# lunchbeats_-_OK.net
KiCad netlist of a schematic drawn in EAGLE
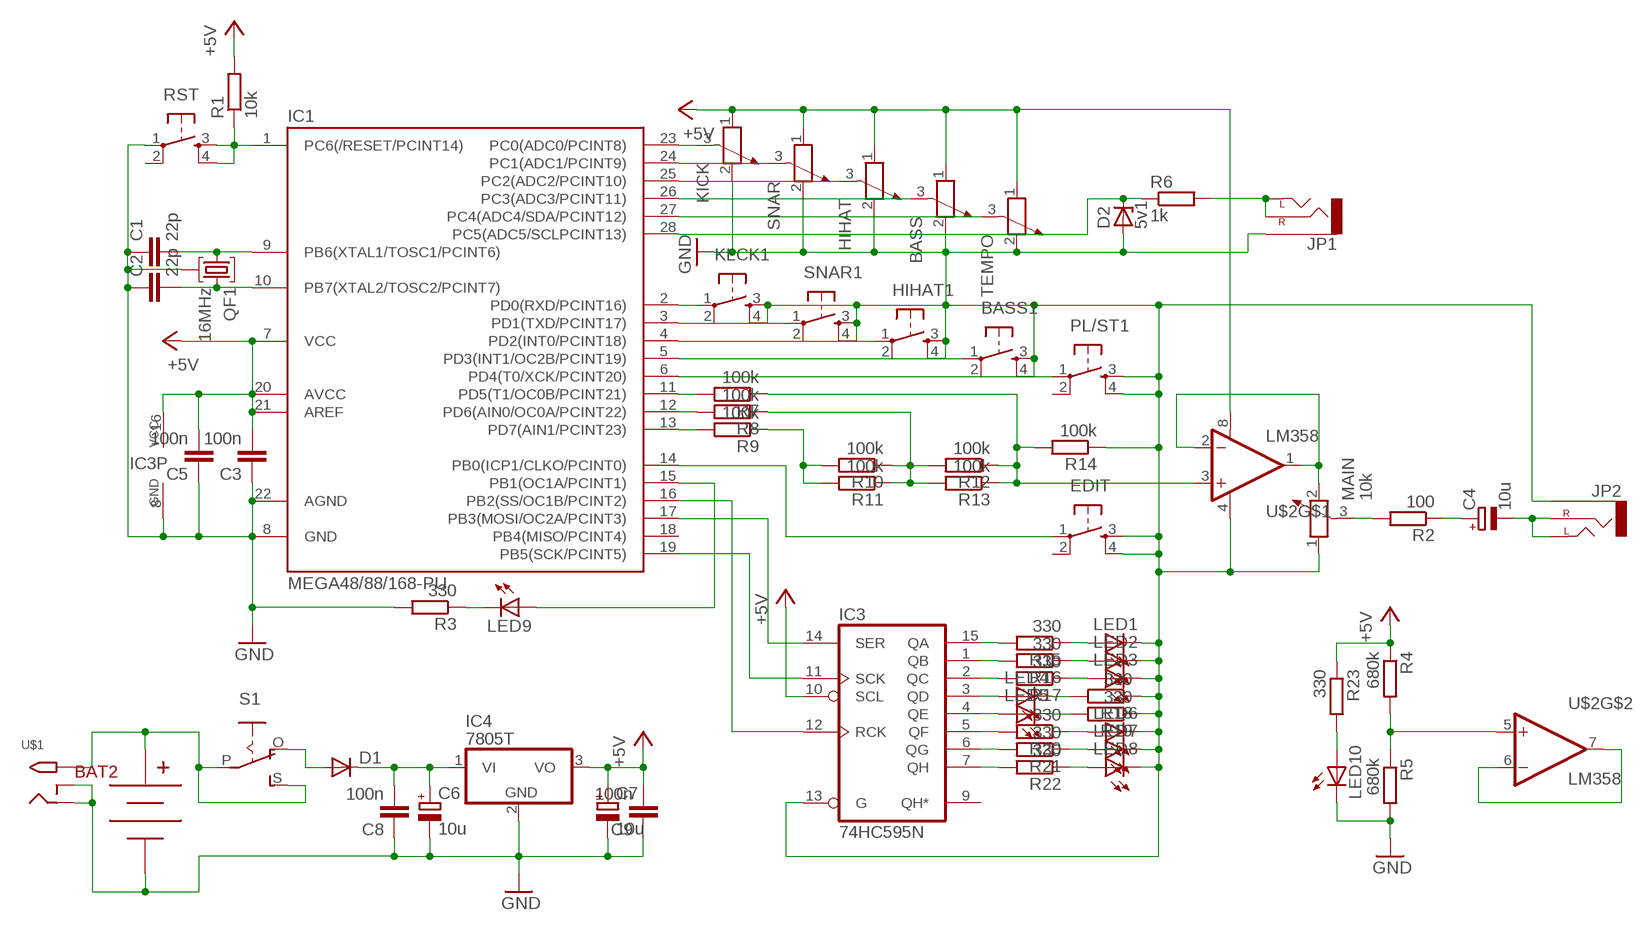
[diagram p0: schematic, sheet 1]

(export (version "E")
  (design (tool "Eeschema 10.0.6"))
  (components
    (comp (ref "BASS")
      (value "POTENTIOMETER_PT-10")
      (footprint "eagle-import:PT-10")
      (libsource (lib "eagle-import") (part "POTENTIOMETER_PT-10"))
    )
    (comp (ref "BASS1")
      (value "TAC_SWITCHPTH")
      (footprint "eagle-import:TACTILE-PTH")
      (libsource (lib "eagle-import") (part "TAC_SWITCHPTH"))
    )
    (comp (ref "BAT2")
      (value "BC9VPCKIT_SOLDERMASK")
      (footprint "eagle-import:BC9VPC_KIT")
      (libsource (lib "eagle-import") (part "BC9VPCKIT_SOLDERMASK"))
    )
    (comp (ref "C1")
      (value "22p")
      (footprint "eagle-import:C025-025X050")
      (libsource (lib "eagle-import") (part "C-EU025-025X050"))
    )
    (comp (ref "C2")
      (value "22p")
      (footprint "eagle-import:C025-025X050")
      (libsource (lib "eagle-import") (part "C-EU025-025X050"))
    )
    (comp (ref "C3")
      (value "100n")
      (footprint "eagle-import:C025-025X050")
      (libsource (lib "eagle-import") (part "C-EU025-025X050"))
    )
    (comp (ref "C4")
      (value "10u")
      (footprint "eagle-import:E2,5-6")
      (libsource (lib "eagle-import") (part "CPOL-EUE2.5-6"))
    )
    (comp (ref "C5")
      (value "100n")
      (footprint "eagle-import:C025-025X050")
      (libsource (lib "eagle-import") (part "C-EU025-025X050"))
    )
    (comp (ref "C6")
      (value "10u")
      (footprint "eagle-import:E2,5-5")
      (libsource (lib "eagle-import") (part "CPOL-EUE2.5-5"))
    )
    (comp (ref "C7")
      (value "10u")
      (footprint "eagle-import:E2,5-5")
      (libsource (lib "eagle-import") (part "CPOL-EUE2.5-5"))
    )
    (comp (ref "C8")
      (value "100n")
      (footprint "eagle-import:C025-025X050")
      (libsource (lib "eagle-import") (part "C-EU025-025X050"))
    )
    (comp (ref "C9")
      (value "100n")
      (footprint "eagle-import:C025-025X050")
      (libsource (lib "eagle-import") (part "C-EU025-025X050"))
    )
    (comp (ref "D1")
      (value "DIODE-D-5")
      (footprint "eagle-import:D-5")
      (libsource (lib "eagle-import") (part "DIODE-D-5"))
    )
    (comp (ref "D2")
      (value "5v1")
      (footprint "eagle-import:ZDIO-2.5")
      (libsource (lib "eagle-import") (part "ZENER-DIODEZD-2.5"))
    )
    (comp (ref "EDIT")
      (value "TAC_SWITCHPTH")
      (footprint "eagle-import:TACTILE-PTH")
      (libsource (lib "eagle-import") (part "TAC_SWITCHPTH"))
    )
    (comp (ref "HIHAT")
      (value "POTENTIOMETER_PT-10")
      (footprint "eagle-import:PT-10")
      (libsource (lib "eagle-import") (part "POTENTIOMETER_PT-10"))
    )
    (comp (ref "HIHAT1")
      (value "TAC_SWITCHPTH")
      (footprint "eagle-import:TACTILE-PTH")
      (libsource (lib "eagle-import") (part "TAC_SWITCHPTH"))
    )
    (comp (ref "IC1")
      (value "MEGA48/88/168-PU")
      (footprint "eagle-import:DIL28-3")
      (libsource (lib "eagle-import") (part "MEGA48/88/168-PU"))
    )
    (comp (ref "IC3")
      (value "74HC595N")
      (footprint "eagle-import:DIL16")
      (libsource (lib "eagle-import") (part "74595NHC"))
    )
    (comp (ref "IC4")
      (value "7805T")
      (footprint "eagle-import:TO220H")
      (libsource (lib "eagle-import") (part "78T05"))
    )
    (comp (ref "JP1")
      (value "AUDIO-JACKPIN-HOLES")
      (footprint "eagle-import:AUDIO-JACK-HOLES")
      (libsource (lib "eagle-import") (part "AUDIO-JACKPIN-HOLES"))
    )
    (comp (ref "JP2")
      (value "AUDIO-JACKPIN-HOLES")
      (footprint "eagle-import:AUDIO-JACK-HOLES")
      (libsource (lib "eagle-import") (part "AUDIO-JACKPIN-HOLES"))
    )
    (comp (ref "KICK")
      (value "POTENTIOMETER_PT-10")
      (footprint "eagle-import:PT-10")
      (libsource (lib "eagle-import") (part "POTENTIOMETER_PT-10"))
    )
    (comp (ref "KLCK1")
      (value "TAC_SWITCHPTH")
      (footprint "eagle-import:TACTILE-PTH")
      (libsource (lib "eagle-import") (part "TAC_SWITCHPTH"))
    )
    (comp (ref "LED1")
      (value "LED5MM")
      (footprint "eagle-import:LED5MM")
      (libsource (lib "eagle-import") (part "LED5MM"))
    )
    (comp (ref "LED2")
      (value "LED5MM")
      (footprint "eagle-import:LED5MM")
      (libsource (lib "eagle-import") (part "LED5MM"))
    )
    (comp (ref "LED3")
      (value "LED5MM")
      (footprint "eagle-import:LED5MM")
      (libsource (lib "eagle-import") (part "LED5MM"))
    )
    (comp (ref "LED4")
      (value "LED5MM")
      (footprint "eagle-import:LED5MM")
      (libsource (lib "eagle-import") (part "LED5MM"))
    )
    (comp (ref "LED5")
      (value "LED5MM")
      (footprint "eagle-import:LED5MM")
      (libsource (lib "eagle-import") (part "LED5MM"))
    )
    (comp (ref "LED6")
      (value "LED5MM")
      (footprint "eagle-import:LED5MM")
      (libsource (lib "eagle-import") (part "LED5MM"))
    )
    (comp (ref "LED7")
      (value "LED5MM")
      (footprint "eagle-import:LED5MM")
      (libsource (lib "eagle-import") (part "LED5MM"))
    )
    (comp (ref "LED8")
      (value "LED5MM")
      (footprint "eagle-import:LED5MM")
      (libsource (lib "eagle-import") (part "LED5MM"))
    )
    (comp (ref "LED9")
      (value "LED5MM")
      (footprint "eagle-import:LED5MM")
      (libsource (lib "eagle-import") (part "LED5MM"))
    )
    (comp (ref "LED10")
      (value "LED5MM")
      (footprint "eagle-import:LED5MM")
      (libsource (lib "eagle-import") (part "LED5MM"))
    )
    (comp (ref "MAIN")
      (value "10k")
      (footprint "eagle-import:PT-10")
      (libsource (lib "eagle-import") (part "POTENTIOMETER_PT-10"))
    )
    (comp (ref "PL/ST1")
      (value "TAC_SWITCHPTH")
      (footprint "eagle-import:TACTILE-PTH")
      (libsource (lib "eagle-import") (part "TAC_SWITCHPTH"))
    )
    (comp (ref "QF1")
      (value "16MHz")
      (footprint "eagle-import:HC49U")
      (libsource (lib "eagle-import") (part "8M10AHC49T"))
    )
    (comp (ref "R1")
      (value "10k")
      (footprint "eagle-import:0204_7")
      (libsource (lib "eagle-import") (part "R-EU_0204/7"))
    )
    (comp (ref "R2")
      (value "100")
      (footprint "eagle-import:0204_7")
      (libsource (lib "eagle-import") (part "R-EU_0204/7"))
    )
    (comp (ref "R3")
      (value "330")
      (footprint "eagle-import:0204_7")
      (libsource (lib "eagle-import") (part "R-EU_0204/7"))
    )
    (comp (ref "R4")
      (value "680k")
      (footprint "eagle-import:0204_5")
      (libsource (lib "eagle-import") (part "R-EU_0204/5"))
    )
    (comp (ref "R5")
      (value "680k")
      (footprint "eagle-import:0204_7")
      (libsource (lib "eagle-import") (part "R-EU_0204/7"))
    )
    (comp (ref "R6")
      (value "1k")
      (footprint "eagle-import:0204_7")
      (libsource (lib "eagle-import") (part "R-EU_0204/7"))
    )
    (comp (ref "R7")
      (value "100k")
      (footprint "eagle-import:0204_7")
      (libsource (lib "eagle-import") (part "R-EU_0204/7"))
    )
    (comp (ref "R8")
      (value "100k")
      (footprint "eagle-import:0204_7")
      (libsource (lib "eagle-import") (part "R-EU_0204/7"))
    )
    (comp (ref "R9")
      (value "100k")
      (footprint "eagle-import:0204_7")
      (libsource (lib "eagle-import") (part "R-EU_0204/7"))
    )
    (comp (ref "R10")
      (value "100k")
      (footprint "eagle-import:0204_7")
      (libsource (lib "eagle-import") (part "R-EU_0204/7"))
    )
    (comp (ref "R11")
      (value "100k")
      (footprint "eagle-import:0204_7")
      (libsource (lib "eagle-import") (part "R-EU_0204/7"))
    )
    (comp (ref "R12")
      (value "100k")
      (footprint "eagle-import:0204_7")
      (libsource (lib "eagle-import") (part "R-EU_0204/7"))
    )
    (comp (ref "R13")
      (value "100k")
      (footprint "eagle-import:0204_7")
      (libsource (lib "eagle-import") (part "R-EU_0204/7"))
    )
    (comp (ref "R14")
      (value "100k")
      (footprint "eagle-import:0204_7")
      (libsource (lib "eagle-import") (part "R-EU_0204/7"))
    )
    (comp (ref "R15")
      (value "330")
      (footprint "eagle-import:0204_7")
      (libsource (lib "eagle-import") (part "R-EU_0204/7"))
    )
    (comp (ref "R16")
      (value "330")
      (footprint "eagle-import:0204_7")
      (libsource (lib "eagle-import") (part "R-EU_0204/7"))
    )
    (comp (ref "R17")
      (value "330")
      (footprint "eagle-import:0204_7")
      (libsource (lib "eagle-import") (part "R-EU_0204/7"))
    )
    (comp (ref "R18")
      (value "330")
      (footprint "eagle-import:0204_7")
      (libsource (lib "eagle-import") (part "R-EU_0204/7"))
    )
    (comp (ref "R19")
      (value "330")
      (footprint "eagle-import:0204_7")
      (libsource (lib "eagle-import") (part "R-EU_0204/7"))
    )
    (comp (ref "R20")
      (value "330")
      (footprint "eagle-import:0204_7")
      (libsource (lib "eagle-import") (part "R-EU_0204/7"))
    )
    (comp (ref "R21")
      (value "330")
      (footprint "eagle-import:0204_7")
      (libsource (lib "eagle-import") (part "R-EU_0204/7"))
    )
    (comp (ref "R22")
      (value "330")
      (footprint "eagle-import:0204_7")
      (libsource (lib "eagle-import") (part "R-EU_0204/7"))
    )
    (comp (ref "R23")
      (value "330")
      (footprint "eagle-import:0204_5")
      (libsource (lib "eagle-import") (part "R-EU_0204/5"))
    )
    (comp (ref "RST")
      (value "TAC_SWITCHPTH")
      (footprint "eagle-import:TACTILE-PTH")
      (libsource (lib "eagle-import") (part "TAC_SWITCHPTH"))
    )
    (comp (ref "S1")
      (value "EG1218S")
      (footprint "eagle-import:EG1218")
      (libsource (lib "eagle-import") (part "EG1218S"))
    )
    (comp (ref "SNAR")
      (value "POTENTIOMETER_PT-10")
      (footprint "eagle-import:PT-10")
      (libsource (lib "eagle-import") (part "POTENTIOMETER_PT-10"))
    )
    (comp (ref "SNAR1")
      (value "TAC_SWITCHPTH")
      (footprint "eagle-import:TACTILE-PTH")
      (libsource (lib "eagle-import") (part "TAC_SWITCHPTH"))
    )
    (comp (ref "TEMPO")
      (value "POTENTIOMETER_PT-10")
      (footprint "eagle-import:PT-10")
      (libsource (lib "eagle-import") (part "POTENTIOMETER_PT-10"))
    )
    (comp (ref "U$1")
      (value "2.1MMJACKTHM")
      (footprint "eagle-import:PJ-102A")
      (libsource (lib "eagle-import") (part "2.1MMJACKTHM"))
    )
    (comp (ref "U$2")
      (value "LM358")
      (footprint "eagle-import:DIP08")
      (libsource (lib "eagle-import") (part "LM358"))
    )
  )
  (nets
    (net (code "1") (name "+5V") (class "Default")
      (node (ref "BASS") (pin "1") (pinfunction "1_1") (pintype "passive"))
      (node (ref "C3") (pin "2") (pinfunction "2_2") (pintype "passive"))
      (node (ref "C5") (pin "2") (pinfunction "2_2") (pintype "passive"))
      (node (ref "C7") (pin "+") (pinfunction "+_+") (pintype "passive"))
      (node (ref "C9") (pin "2") (pinfunction "2_2") (pintype "passive"))
      (node (ref "HIHAT") (pin "1") (pinfunction "1_1") (pintype "passive"))
      (node (ref "IC1") (pin "20") (pinfunction "AVCC_20") (pintype "passive"))
      (node (ref "IC1") (pin "21") (pinfunction "AREF_21") (pintype "passive"))
      (node (ref "IC1") (pin "7") (pinfunction "VCC_7") (pintype "power_in"))
      (node (ref "IC3") (pin "10") (pinfunction "SCL_10") (pintype "input"))
      (node (ref "IC3") (pin "16") (pinfunction "VCC_16") (pintype "power_in"))
      (node (ref "IC4") (pin "3") (pinfunction "VO_3") (pintype "passive"))
      (node (ref "KICK") (pin "1") (pinfunction "1_1") (pintype "passive"))
      (node (ref "R1") (pin "2") (pinfunction "2_2") (pintype "passive"))
      (node (ref "R23") (pin "1") (pinfunction "1_1") (pintype "passive"))
      (node (ref "R4") (pin "1") (pinfunction "1_1") (pintype "passive"))
      (node (ref "SNAR") (pin "1") (pinfunction "1_1") (pintype "passive"))
      (node (ref "TEMPO") (pin "1") (pinfunction "1_1") (pintype "passive"))
      (node (ref "U$2") (pin "8") (pinfunction "V+_8") (pintype "power_in"))
    )
    (net (code "2") (name "GND") (class "Default")
      (node (ref "BASS") (pin "2") (pinfunction "2_2") (pintype "passive"))
      (node (ref "BASS1") (pin "3") (pinfunction "3_3") (pintype "passive"))
      (node (ref "BASS1") (pin "4") (pinfunction "4_4") (pintype "passive"))
      (node (ref "BAT2") (pin "V+") (pinfunction "V-_V+") (pintype "bidirectional"))
      (node (ref "C1") (pin "1") (pinfunction "1_1") (pintype "passive"))
      (node (ref "C2") (pin "1") (pinfunction "1_1") (pintype "passive"))
      (node (ref "C3") (pin "1") (pinfunction "1_1") (pintype "passive"))
      (node (ref "C5") (pin "1") (pinfunction "1_1") (pintype "passive"))
      (node (ref "C6") (pin "-") (pinfunction "-_-") (pintype "passive"))
      (node (ref "C7") (pin "-") (pinfunction "-_-") (pintype "passive"))
      (node (ref "C8") (pin "1") (pinfunction "1_1") (pintype "passive"))
      (node (ref "C9") (pin "1") (pinfunction "1_1") (pintype "passive"))
      (node (ref "D2") (pin "A") (pinfunction "A_A") (pintype "passive"))
      (node (ref "EDIT") (pin "3") (pinfunction "3_3") (pintype "passive"))
      (node (ref "EDIT") (pin "4") (pinfunction "4_4") (pintype "passive"))
      (node (ref "HIHAT") (pin "2") (pinfunction "2_2") (pintype "passive"))
      (node (ref "HIHAT1") (pin "3") (pinfunction "3_3") (pintype "passive"))
      (node (ref "HIHAT1") (pin "4") (pinfunction "4_4") (pintype "passive"))
      (node (ref "IC1") (pin "22") (pinfunction "AGND_22") (pintype "power_in"))
      (node (ref "IC1") (pin "8") (pinfunction "GND_8") (pintype "power_in"))
      (node (ref "IC3") (pin "13") (pinfunction "G_13") (pintype "input"))
      (node (ref "IC3") (pin "8") (pinfunction "GND_8") (pintype "power_in"))
      (node (ref "IC4") (pin "2") (pinfunction "GND_2") (pintype "passive"))
      (node (ref "JP1") (pin "GND") (pinfunction "SLEEVE_GND") (pintype "bidirectional"))
      (node (ref "JP2") (pin "GND") (pinfunction "SLEEVE_GND") (pintype "bidirectional"))
      (node (ref "KICK") (pin "2") (pinfunction "2_2") (pintype "passive"))
      (node (ref "KLCK1") (pin "3") (pinfunction "3_3") (pintype "passive"))
      (node (ref "KLCK1") (pin "4") (pinfunction "4_4") (pintype "passive"))
      (node (ref "LED1") (pin "K") (pinfunction "C_K") (pintype "passive"))
      (node (ref "LED10") (pin "K") (pinfunction "C_K") (pintype "passive"))
      (node (ref "LED2") (pin "K") (pinfunction "C_K") (pintype "passive"))
      (node (ref "LED3") (pin "K") (pinfunction "C_K") (pintype "passive"))
      (node (ref "LED6") (pin "K") (pinfunction "C_K") (pintype "passive"))
      (node (ref "LED7") (pin "K") (pinfunction "C_K") (pintype "passive"))
      (node (ref "LED8") (pin "K") (pinfunction "C_K") (pintype "passive"))
      (node (ref "MAIN") (pin "1") (pinfunction "1_1") (pintype "passive"))
      (node (ref "PL/ST1") (pin "3") (pinfunction "3_3") (pintype "passive"))
      (node (ref "PL/ST1") (pin "4") (pinfunction "4_4") (pintype "passive"))
      (node (ref "QF1") (pin "2") (pinfunction "2_2") (pintype "passive"))
      (node (ref "R14") (pin "1") (pinfunction "1_1") (pintype "passive"))
      (node (ref "R18") (pin "1") (pinfunction "1_1") (pintype "passive"))
      (node (ref "R19") (pin "1") (pinfunction "1_1") (pintype "passive"))
      (node (ref "R3") (pin "2") (pinfunction "2_2") (pintype "passive"))
      (node (ref "R5") (pin "2") (pinfunction "2_2") (pintype "passive"))
      (node (ref "RST") (pin "1") (pinfunction "1_1") (pintype "passive"))
      (node (ref "SNAR") (pin "2") (pinfunction "2_2") (pintype "passive"))
      (node (ref "SNAR1") (pin "3") (pinfunction "3_3") (pintype "passive"))
      (node (ref "SNAR1") (pin "4") (pinfunction "4_4") (pintype "passive"))
      (node (ref "TEMPO") (pin "2") (pinfunction "2_2") (pintype "passive"))
      (node (ref "U$1") (pin "RING") (pinfunction "RING_RING") (pintype "bidirectional"))
      (node (ref "U$1") (pin "RING_SW") (pinfunction "RING_SW_RING_SW") (pintype "bidirectional"))
      (node (ref "U$2") (pin "4") (pinfunction "V-_4") (pintype "power_in"))
    )
    (net (code "3") (name "Net-(BAT2-V+)") (class "Default")
      (node (ref "BAT2") (pin "V-") (pinfunction "V+_V-") (pintype "bidirectional"))
      (node (ref "S1") (pin "P") (pinfunction "P_P") (pintype "passive"))
      (node (ref "S1") (pin "S") (pinfunction "S_S") (pintype "passive"))
      (node (ref "U$1") (pin "TIP") (pinfunction "TIP_TIP") (pintype "bidirectional"))
    )
    (net (code "4") (name "Net-(C4-Pad+)") (class "Default")
      (node (ref "C4") (pin "+") (pinfunction "+_+") (pintype "passive"))
      (node (ref "R2") (pin "1") (pinfunction "1_1") (pintype "passive"))
    )
    (net (code "5") (name "Net-(D1-PadA)") (class "Default")
      (node (ref "D1") (pin "A") (pinfunction "A_A") (pintype "passive"))
      (node (ref "S1") (pin "O") (pinfunction "O_O") (pintype "passive"))
    )
    (net (code "6") (name "Net-(IC1-PB0(ICP1{slash}CLKO{slash}PCINT0))") (class "Default")
      (node (ref "EDIT") (pin "1") (pinfunction "1_1") (pintype "passive"))
      (node (ref "IC1") (pin "14") (pinfunction "PB0(ICP1/CLKO/PCINT0)_14") (pintype "bidirectional"))
    )
    (net (code "7") (name "Net-(IC1-PB1(OC1A{slash}PCINT1))") (class "Default")
      (node (ref "IC1") (pin "15") (pinfunction "PB1(OC1A/PCINT1)_15") (pintype "bidirectional"))
      (node (ref "LED9") (pin "A") (pinfunction "A_A") (pintype "passive"))
    )
    (net (code "8") (name "Net-(IC1-PB2(SS{slash}OC1B{slash}PCINT2))") (class "Default")
      (node (ref "IC1") (pin "16") (pinfunction "PB2(SS/OC1B/PCINT2)_16") (pintype "bidirectional"))
      (node (ref "IC3") (pin "12") (pinfunction "RCK_12") (pintype "input"))
    )
    (net (code "9") (name "Net-(IC1-PB3(MOSI{slash}OC2A{slash}PCINT3))") (class "Default")
      (node (ref "IC1") (pin "17") (pinfunction "PB3(MOSI/OC2A/PCINT3)_17") (pintype "bidirectional"))
      (node (ref "IC3") (pin "14") (pinfunction "SER_14") (pintype "input"))
    )
    (net (code "10") (name "Net-(IC1-PB5(SCK{slash}PCINT5))") (class "Default")
      (node (ref "IC1") (pin "19") (pinfunction "PB5(SCK/PCINT5)_19") (pintype "bidirectional"))
      (node (ref "IC3") (pin "11") (pinfunction "SCK_11") (pintype "input"))
    )
    (net (code "11") (name "Net-(IC1-PB6(XTAL1{slash}TOSC1{slash}PCINT6))") (class "Default")
      (node (ref "C1") (pin "2") (pinfunction "2_2") (pintype "passive"))
      (node (ref "IC1") (pin "9") (pinfunction "PB6(XTAL1/TOSC1/PCINT6)_9") (pintype "bidirectional"))
      (node (ref "QF1") (pin "1") (pinfunction "1_1") (pintype "passive"))
    )
    (net (code "12") (name "Net-(IC1-PB7(XTAL2{slash}TOSC2{slash}PCINT7))") (class "Default")
      (node (ref "C2") (pin "2") (pinfunction "2_2") (pintype "passive"))
      (node (ref "IC1") (pin "10") (pinfunction "PB7(XTAL2/TOSC2/PCINT7)_10") (pintype "bidirectional"))
      (node (ref "QF1") (pin "3") (pinfunction "3_3") (pintype "passive"))
    )
    (net (code "13") (name "Net-(IC1-PC0(ADC0{slash}PCINT8))") (class "Default")
      (node (ref "IC1") (pin "23") (pinfunction "PC0(ADC0/PCINT8)_23") (pintype "bidirectional"))
      (node (ref "KICK") (pin "3") (pinfunction "3_3") (pintype "passive"))
    )
    (net (code "14") (name "Net-(IC1-PC1(ADC1{slash}PCINT9))") (class "Default")
      (node (ref "IC1") (pin "24") (pinfunction "PC1(ADC1/PCINT9)_24") (pintype "bidirectional"))
      (node (ref "SNAR") (pin "3") (pinfunction "3_3") (pintype "passive"))
    )
    (net (code "15") (name "Net-(IC1-PC2(ADC2{slash}PCINT10))") (class "Default")
      (node (ref "HIHAT") (pin "3") (pinfunction "3_3") (pintype "passive"))
      (node (ref "IC1") (pin "25") (pinfunction "PC2(ADC2/PCINT10)_25") (pintype "bidirectional"))
    )
    (net (code "16") (name "Net-(IC1-PC3(ADC3{slash}PCINT11))") (class "Default")
      (node (ref "BASS") (pin "3") (pinfunction "3_3") (pintype "passive"))
      (node (ref "IC1") (pin "26") (pinfunction "PC3(ADC3/PCINT11)_26") (pintype "bidirectional"))
    )
    (net (code "17") (name "Net-(IC1-PC4(ADC4{slash}SDA{slash}PCINT12))") (class "Default")
      (node (ref "IC1") (pin "27") (pinfunction "PC4(ADC4/SDA/PCINT12)_27") (pintype "bidirectional"))
      (node (ref "TEMPO") (pin "3") (pinfunction "3_3") (pintype "passive"))
    )
    (net (code "18") (name "Net-(IC1-PC5(ADC5{slash}SCLPCINT13))") (class "Default")
      (node (ref "D2") (pin "C") (pinfunction "C_C") (pintype "passive"))
      (node (ref "IC1") (pin "28") (pinfunction "PC5(ADC5/SCLPCINT13)_28") (pintype "bidirectional"))
      (node (ref "R6") (pin "1") (pinfunction "1_1") (pintype "passive"))
    )
    (net (code "19") (name "Net-(IC1-PC6({slash}RESET{slash}PCINT14))") (class "Default")
      (node (ref "IC1") (pin "1") (pinfunction "PC6(/RESET/PCINT14)_1") (pintype "bidirectional"))
      (node (ref "R1") (pin "1") (pinfunction "1_1") (pintype "passive"))
      (node (ref "RST") (pin "3") (pinfunction "3_3") (pintype "passive"))
      (node (ref "RST") (pin "4") (pinfunction "4_4") (pintype "passive"))
    )
    (net (code "20") (name "Net-(IC1-PD0(RXD{slash}PCINT16))") (class "Default")
      (node (ref "IC1") (pin "2") (pinfunction "PD0(RXD/PCINT16)_2") (pintype "bidirectional"))
      (node (ref "KLCK1") (pin "1") (pinfunction "1_1") (pintype "passive"))
    )
    (net (code "21") (name "Net-(IC1-PD1(TXD{slash}PCINT17))") (class "Default")
      (node (ref "IC1") (pin "3") (pinfunction "PD1(TXD/PCINT17)_3") (pintype "bidirectional"))
      (node (ref "SNAR1") (pin "1") (pinfunction "1_1") (pintype "passive"))
    )
    (net (code "22") (name "Net-(IC1-PD2(INT0{slash}PCINT18))") (class "Default")
      (node (ref "HIHAT1") (pin "1") (pinfunction "1_1") (pintype "passive"))
      (node (ref "IC1") (pin "4") (pinfunction "PD2(INT0/PCINT18)_4") (pintype "bidirectional"))
    )
    (net (code "23") (name "Net-(IC1-PD3(INT1{slash}OC2B{slash}PCINT19))") (class "Default")
      (node (ref "BASS1") (pin "1") (pinfunction "1_1") (pintype "passive"))
      (node (ref "IC1") (pin "5") (pinfunction "PD3(INT1/OC2B/PCINT19)_5") (pintype "bidirectional"))
    )
    (net (code "24") (name "Net-(IC1-PD4(T0{slash}XCK{slash}PCINT20))") (class "Default")
      (node (ref "IC1") (pin "6") (pinfunction "PD4(T0/XCK/PCINT20)_6") (pintype "bidirectional"))
      (node (ref "PL/ST1") (pin "1") (pinfunction "1_1") (pintype "passive"))
    )
    (net (code "25") (name "Net-(IC1-PD5(T1{slash}OC0B{slash}PCINT21))") (class "Default")
      (node (ref "IC1") (pin "11") (pinfunction "PD5(T1/OC0B/PCINT21)_11") (pintype "bidirectional"))
      (node (ref "R7") (pin "2") (pinfunction "2_2") (pintype "passive"))
    )
    (net (code "26") (name "Net-(IC1-PD6(AIN0{slash}OC0A{slash}PCINT22))") (class "Default")
      (node (ref "IC1") (pin "12") (pinfunction "PD6(AIN0/OC0A/PCINT22)_12") (pintype "bidirectional"))
      (node (ref "R8") (pin "2") (pinfunction "2_2") (pintype "passive"))
    )
    (net (code "27") (name "Net-(IC1-PD7(AIN1{slash}PCINT23))") (class "Default")
      (node (ref "IC1") (pin "13") (pinfunction "PD7(AIN1/PCINT23)_13") (pintype "bidirectional"))
      (node (ref "R9") (pin "2") (pinfunction "2_2") (pintype "passive"))
    )
    (net (code "28") (name "Net-(IC3A-QA)") (class "Default")
      (node (ref "IC3") (pin "15") (pinfunction "QA_15") (pintype "tri_state"))
      (node (ref "R15") (pin "2") (pinfunction "2_2") (pintype "passive"))
    )
    (net (code "29") (name "Net-(IC3A-QB)") (class "Default")
      (node (ref "IC3") (pin "1") (pinfunction "QB_1") (pintype "tri_state"))
      (node (ref "R16") (pin "2") (pinfunction "2_2") (pintype "passive"))
    )
    (net (code "30") (name "Net-(IC3A-QC)") (class "Default")
      (node (ref "IC3") (pin "2") (pinfunction "QC_2") (pintype "tri_state"))
      (node (ref "R17") (pin "2") (pinfunction "2_2") (pintype "passive"))
    )
    (net (code "31") (name "Net-(IC3A-QD)") (class "Default")
      (node (ref "IC3") (pin "3") (pinfunction "QD_3") (pintype "tri_state"))
      (node (ref "LED4") (pin "A") (pinfunction "A_A") (pintype "passive"))
    )
    (net (code "32") (name "Net-(IC3A-QE)") (class "Default")
      (node (ref "IC3") (pin "4") (pinfunction "QE_4") (pintype "tri_state"))
      (node (ref "LED5") (pin "A") (pinfunction "A_A") (pintype "passive"))
    )
    (net (code "33") (name "Net-(IC3A-QF)") (class "Default")
      (node (ref "IC3") (pin "5") (pinfunction "QF_5") (pintype "tri_state"))
      (node (ref "R20") (pin "2") (pinfunction "2_2") (pintype "passive"))
    )
    (net (code "34") (name "Net-(IC3A-QG)") (class "Default")
      (node (ref "IC3") (pin "6") (pinfunction "QG_6") (pintype "tri_state"))
      (node (ref "R21") (pin "2") (pinfunction "2_2") (pintype "passive"))
    )
    (net (code "35") (name "Net-(IC3A-QH)") (class "Default")
      (node (ref "IC3") (pin "7") (pinfunction "QH_7") (pintype "tri_state"))
      (node (ref "R22") (pin "2") (pinfunction "2_2") (pintype "passive"))
    )
    (net (code "36") (name "Net-(IC4-VI)") (class "Default")
      (node (ref "C6") (pin "+") (pinfunction "+_+") (pintype "passive"))
      (node (ref "C8") (pin "2") (pinfunction "2_2") (pintype "passive"))
      (node (ref "D1") (pin "C") (pinfunction "C_C") (pintype "passive"))
      (node (ref "IC4") (pin "1") (pinfunction "VI_1") (pintype "input"))
    )
    (net (code "37") (name "Net-(JP1-RIGHT)") (class "Default")
      (node (ref "JP1") (pin "L1-") (pinfunction "LEFT_L1-") (pintype "bidirectional"))
      (node (ref "JP1") (pin "L2-") (pinfunction "LEFT_L2-") (pintype "bidirectional"))
      (node (ref "JP1") (pin "R+") (pinfunction "RIGHT_R+") (pintype "bidirectional"))
      (node (ref "R6") (pin "2") (pinfunction "2_2") (pintype "passive"))
    )
    (net (code "38") (name "Net-(JP2-RIGHT)") (class "Default")
      (node (ref "C4") (pin "-") (pinfunction "-_-") (pintype "passive"))
      (node (ref "JP2") (pin "L1-") (pinfunction "LEFT_L1-") (pintype "bidirectional"))
      (node (ref "JP2") (pin "L2-") (pinfunction "LEFT_L2-") (pintype "bidirectional"))
      (node (ref "JP2") (pin "R+") (pinfunction "RIGHT_R+") (pintype "bidirectional"))
    )
    (net (code "39") (name "Net-(LED1-PadA)") (class "Default")
      (node (ref "LED1") (pin "A") (pinfunction "A_A") (pintype "passive"))
      (node (ref "R15") (pin "1") (pinfunction "1_1") (pintype "passive"))
    )
    (net (code "40") (name "Net-(LED2-PadA)") (class "Default")
      (node (ref "LED2") (pin "A") (pinfunction "A_A") (pintype "passive"))
      (node (ref "R16") (pin "1") (pinfunction "1_1") (pintype "passive"))
    )
    (net (code "41") (name "Net-(LED3-PadA)") (class "Default")
      (node (ref "LED3") (pin "A") (pinfunction "A_A") (pintype "passive"))
      (node (ref "R17") (pin "1") (pinfunction "1_1") (pintype "passive"))
    )
    (net (code "42") (name "Net-(LED4-C)") (class "Default")
      (node (ref "LED4") (pin "K") (pinfunction "C_K") (pintype "passive"))
      (node (ref "R18") (pin "2") (pinfunction "2_2") (pintype "passive"))
    )
    (net (code "43") (name "Net-(LED5-C)") (class "Default")
      (node (ref "LED5") (pin "K") (pinfunction "C_K") (pintype "passive"))
      (node (ref "R19") (pin "2") (pinfunction "2_2") (pintype "passive"))
    )
    (net (code "44") (name "Net-(LED6-PadA)") (class "Default")
      (node (ref "LED6") (pin "A") (pinfunction "A_A") (pintype "passive"))
      (node (ref "R20") (pin "1") (pinfunction "1_1") (pintype "passive"))
    )
    (net (code "45") (name "Net-(LED7-PadA)") (class "Default")
      (node (ref "LED7") (pin "A") (pinfunction "A_A") (pintype "passive"))
      (node (ref "R21") (pin "1") (pinfunction "1_1") (pintype "passive"))
    )
    (net (code "46") (name "Net-(LED8-PadA)") (class "Default")
      (node (ref "LED8") (pin "A") (pinfunction "A_A") (pintype "passive"))
      (node (ref "R22") (pin "1") (pinfunction "1_1") (pintype "passive"))
    )
    (net (code "47") (name "Net-(LED9-C)") (class "Default")
      (node (ref "LED9") (pin "K") (pinfunction "C_K") (pintype "passive"))
      (node (ref "R3") (pin "1") (pinfunction "1_1") (pintype "passive"))
    )
    (net (code "48") (name "Net-(LED10-PadA)") (class "Default")
      (node (ref "LED10") (pin "A") (pinfunction "A_A") (pintype "passive"))
      (node (ref "R23") (pin "2") (pinfunction "2_2") (pintype "passive"))
    )
    (net (code "49") (name "Net-(MAIN-Pad3)") (class "Default")
      (node (ref "MAIN") (pin "3") (pinfunction "3_3") (pintype "passive"))
      (node (ref "R2") (pin "2") (pinfunction "2_2") (pintype "passive"))
    )
    (net (code "50") (name "Net-(R10-Pad1)") (class "Default")
      (node (ref "R10") (pin "1") (pinfunction "1_1") (pintype "passive"))
      (node (ref "R11") (pin "1") (pinfunction "1_1") (pintype "passive"))
      (node (ref "R12") (pin "2") (pinfunction "2_2") (pintype "passive"))
      (node (ref "R13") (pin "2") (pinfunction "2_2") (pintype "passive"))
      (node (ref "R8") (pin "1") (pinfunction "1_1") (pintype "passive"))
    )
    (net (code "51") (name "Net-(R10-Pad2)") (class "Default")
      (node (ref "R10") (pin "2") (pinfunction "2_2") (pintype "passive"))
      (node (ref "R11") (pin "2") (pinfunction "2_2") (pintype "passive"))
      (node (ref "R9") (pin "1") (pinfunction "1_1") (pintype "passive"))
    )
    (net (code "52") (name "Net-(U$2A-+IN)") (class "Default")
      (node (ref "R12") (pin "1") (pinfunction "1_1") (pintype "passive"))
      (node (ref "R13") (pin "1") (pinfunction "1_1") (pintype "passive"))
      (node (ref "R14") (pin "2") (pinfunction "2_2") (pintype "passive"))
      (node (ref "R7") (pin "1") (pinfunction "1_1") (pintype "passive"))
      (node (ref "U$2") (pin "3") (pinfunction "+IN_3") (pintype "input"))
    )
    (net (code "53") (name "Net-(U$2A--IN)") (class "Default")
      (node (ref "MAIN") (pin "2") (pinfunction "2_2") (pintype "passive"))
      (node (ref "U$2") (pin "1") (pinfunction "OUT_1") (pintype "output"))
      (node (ref "U$2") (pin "2") (pinfunction "-IN_2") (pintype "input"))
    )
    (net (code "54") (name "Net-(U$2B-+IN)") (class "Default")
      (node (ref "R4") (pin "2") (pinfunction "2_2") (pintype "passive"))
      (node (ref "R5") (pin "1") (pinfunction "1_1") (pintype "passive"))
      (node (ref "U$2") (pin "5") (pinfunction "+IN_5") (pintype "input"))
    )
    (net (code "55") (name "Net-(U$2B--IN)") (class "Default")
      (node (ref "U$2") (pin "6") (pinfunction "-IN_6") (pintype "input"))
      (node (ref "U$2") (pin "7") (pinfunction "OUT_7") (pintype "output"))
    )
    (net (code "56") (name "unconnected-(BASS1-Pad2)") (class "Default")
      (node (ref "BASS1") (pin "2") (pinfunction "2_2") (pintype "passive"))
    )
    (net (code "57") (name "unconnected-(EDIT-Pad2)") (class "Default")
      (node (ref "EDIT") (pin "2") (pinfunction "2_2") (pintype "passive"))
    )
    (net (code "58") (name "unconnected-(HIHAT1-Pad2)") (class "Default")
      (node (ref "HIHAT1") (pin "2") (pinfunction "2_2") (pintype "passive"))
    )
    (net (code "59") (name "unconnected-(IC1-PB4(MISO{slash}PCINT4)-Pad18)") (class "Default")
      (node (ref "IC1") (pin "18") (pinfunction "PB4(MISO/PCINT4)_18") (pintype "bidirectional"))
    )
    (net (code "60") (name "unconnected-(IC3A-QH*-Pad9)") (class "Default")
      (node (ref "IC3") (pin "9") (pinfunction "QH*_9") (pintype "tri_state"))
    )
    (net (code "61") (name "unconnected-(KLCK1-Pad2)") (class "Default")
      (node (ref "KLCK1") (pin "2") (pinfunction "2_2") (pintype "passive"))
    )
    (net (code "62") (name "unconnected-(PL/ST1-Pad2)") (class "Default")
      (node (ref "PL/ST1") (pin "2") (pinfunction "2_2") (pintype "passive"))
    )
    (net (code "63") (name "unconnected-(RST-Pad2)") (class "Default")
      (node (ref "RST") (pin "2") (pinfunction "2_2") (pintype "passive"))
    )
    (net (code "64") (name "unconnected-(SNAR1-Pad2)") (class "Default")
      (node (ref "SNAR1") (pin "2") (pinfunction "2_2") (pintype "passive"))
    )
  )
)
